# dhtsensor.net
KiCad netlist of a schematic drawn in EAGLE
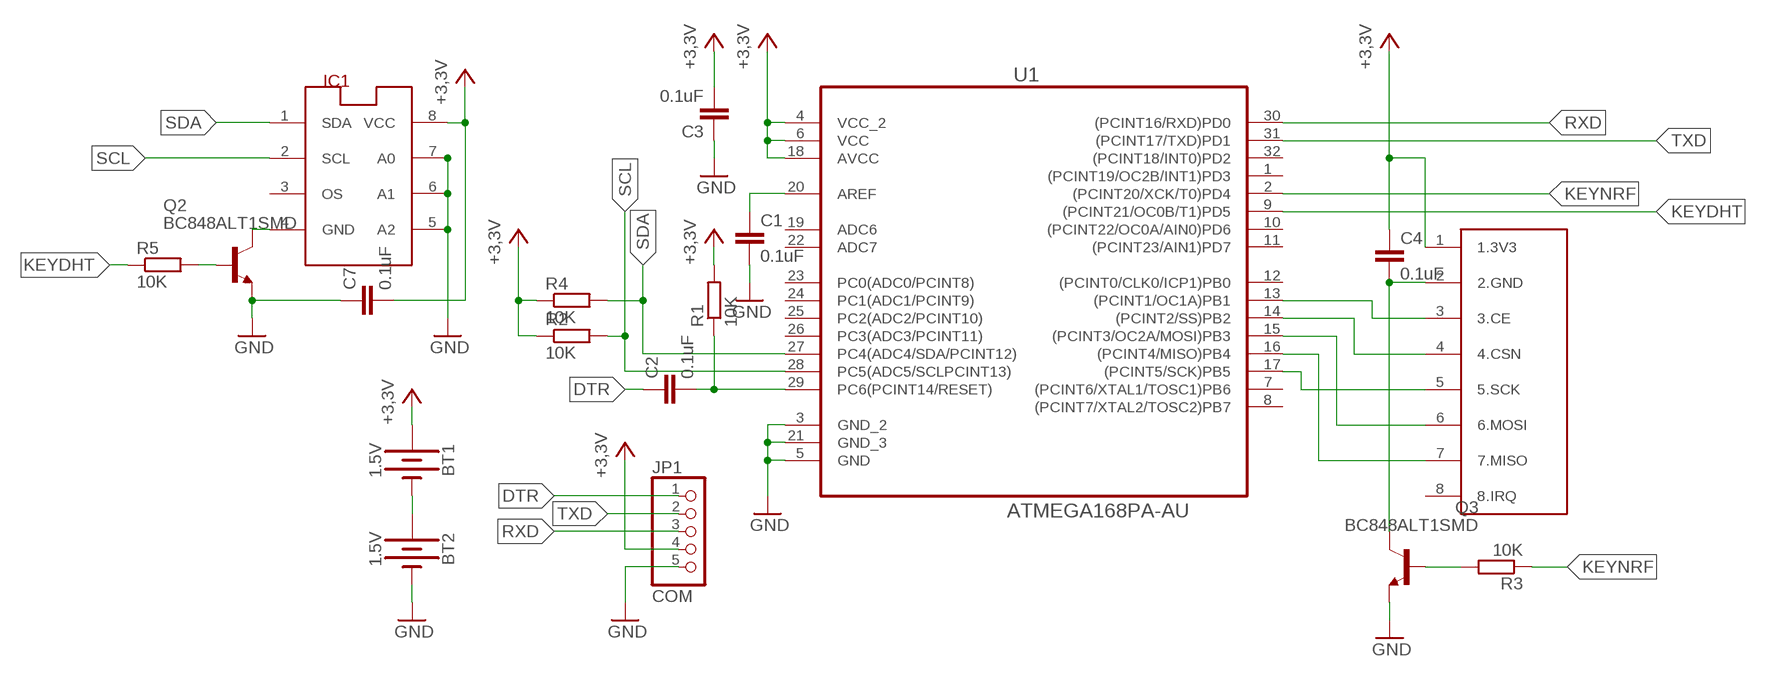
[diagram p0: schematic, sheet 1]

(export (version "E")
  (design (tool "Eeschema 10.0.6"))
  (components
    (comp (ref "BT1")
      (value "1.5V")
      (footprint "eagle-import:BATTERY-AAA-KIT")
      (libsource (lib "eagle-import") (part "BATTERY-AAA_KIT"))
    )
    (comp (ref "BT2")
      (value "1.5V")
      (footprint "eagle-import:BATTERY-AAA-KIT")
      (libsource (lib "eagle-import") (part "BATTERY-AAA_KIT"))
    )
    (comp (ref "C1")
      (value "0.1uF")
      (footprint "eagle-import:C1206")
      (libsource (lib "eagle-import") (part "C-EUC1206"))
    )
    (comp (ref "C2")
      (value "0.1uF")
      (footprint "eagle-import:C1206")
      (libsource (lib "eagle-import") (part "C-EUC1206"))
    )
    (comp (ref "C3")
      (value "0.1uF")
      (footprint "eagle-import:C1206")
      (libsource (lib "eagle-import") (part "C-EUC1206"))
    )
    (comp (ref "C4")
      (value "0.1uF")
      (footprint "eagle-import:C1206")
      (libsource (lib "eagle-import") (part "C-EUC1206"))
    )
    (comp (ref "C7")
      (value "0.1uF")
      (footprint "eagle-import:C1206")
      (libsource (lib "eagle-import") (part "C-EUC1206"))
    )
    (comp (ref "IC1")
      (value "LM75_ICN")
      (footprint "eagle-import:SO8_LM75")
      (libsource (lib "eagle-import") (part "LM75_ICN"))
    )
    (comp (ref "JP1")
      (value "COM")
      (footprint "eagle-import:1X05")
      (libsource (lib "eagle-import") (part "PINHD-1X5"))
    )
    (comp (ref "Q2")
      (value "BC848ALT1SMD")
      (footprint "eagle-import:SOT23")
      (libsource (lib "eagle-import") (part "BC848SMDALT1"))
    )
    (comp (ref "Q3")
      (value "BC848ALT1SMD")
      (footprint "eagle-import:SOT23")
      (libsource (lib "eagle-import") (part "BC848SMDALT1"))
    )
    (comp (ref "R1")
      (value "10K")
      (footprint "eagle-import:R1206")
      (libsource (lib "eagle-import") (part "R-EU_R1206"))
    )
    (comp (ref "R2")
      (value "10K")
      (footprint "eagle-import:R1206")
      (libsource (lib "eagle-import") (part "R-EU_R1206"))
    )
    (comp (ref "R3")
      (value "10K")
      (footprint "eagle-import:R1206")
      (libsource (lib "eagle-import") (part "R-EU_R1206"))
    )
    (comp (ref "R4")
      (value "10K")
      (footprint "eagle-import:R1206")
      (libsource (lib "eagle-import") (part "R-EU_R1206"))
    )
    (comp (ref "R5")
      (value "10K")
      (footprint "eagle-import:R1206")
      (libsource (lib "eagle-import") (part "R-EU_R1206"))
    )
    (comp (ref "U$9")
      (value "NRF24L01+")
      (footprint "eagle-import:NRF24L01+")
      (libsource (lib "eagle-import") (part "NRF24L01+"))
    )
    (comp (ref "U1")
      (value "ATMEGA168PA-AU")
      (footprint "eagle-import:QFP80P900X900X120-32N")
      (fields (field (name "MF") "Atmel"))
      (libsource (lib "eagle-import") (part "ATMEGA168PA-AU"))
    )
  )
  (nets
    (net (code "1") (name "+3,3V") (class "Default")
      (node (ref "BT1") (pin "PWR@1") (pinfunction "+_PWR@1") (pintype "power_in"))
      (node (ref "C3") (pin "2") (pinfunction "2_2") (pintype "passive"))
      (node (ref "C4") (pin "1") (pinfunction "1_1") (pintype "passive"))
      (node (ref "C7") (pin "2") (pinfunction "2_2") (pintype "passive"))
      (node (ref "IC1") (pin "8") (pinfunction "VCC_8") (pintype "power_in"))
      (node (ref "JP1") (pin "4") (pinfunction "4_4") (pintype "passive"))
      (node (ref "R1") (pin "2") (pinfunction "2_2") (pintype "passive"))
      (node (ref "R2") (pin "1") (pinfunction "1_1") (pintype "passive"))
      (node (ref "R4") (pin "1") (pinfunction "1_1") (pintype "passive"))
      (node (ref "U$9") (pin "1") (pinfunction "1.3V3_1") (pintype "bidirectional"))
      (node (ref "U1") (pin "18") (pinfunction "AVCC_18") (pintype "power_in"))
      (node (ref "U1") (pin "4") (pinfunction "VCC_2_4") (pintype "power_in"))
      (node (ref "U1") (pin "6") (pinfunction "VCC_6") (pintype "power_in"))
    )
    (net (code "2") (name "DTR") (class "Default")
      (node (ref "C2") (pin "1") (pinfunction "1_1") (pintype "passive"))
      (node (ref "JP1") (pin "1") (pinfunction "1_1") (pintype "passive"))
    )
    (net (code "3") (name "GND") (class "Default")
      (node (ref "BT2") (pin "GND@1") (pinfunction "-_GND@1") (pintype "power_in"))
      (node (ref "C1") (pin "2") (pinfunction "2_2") (pintype "passive"))
      (node (ref "C3") (pin "1") (pinfunction "1_1") (pintype "passive"))
      (node (ref "C7") (pin "1") (pinfunction "1_1") (pintype "passive"))
      (node (ref "IC1") (pin "5") (pinfunction "A2_5") (pintype "input"))
      (node (ref "IC1") (pin "6") (pinfunction "A1_6") (pintype "input"))
      (node (ref "IC1") (pin "7") (pinfunction "A0_7") (pintype "input"))
      (node (ref "JP1") (pin "5") (pinfunction "5_5") (pintype "passive"))
      (node (ref "Q2") (pin "2") (pinfunction "E_2") (pintype "passive"))
      (node (ref "Q3") (pin "2") (pinfunction "E_2") (pintype "passive"))
      (node (ref "U1") (pin "21") (pinfunction "GND_3_21") (pintype "passive"))
      (node (ref "U1") (pin "3") (pinfunction "GND_2_3") (pintype "passive"))
      (node (ref "U1") (pin "5") (pinfunction "GND_5") (pintype "passive"))
    )
    (net (code "4") (name "KEYDHT") (class "Default")
      (node (ref "R5") (pin "1") (pinfunction "1_1") (pintype "passive"))
      (node (ref "U1") (pin "9") (pinfunction "(PCINT21/OC0B/T1)PD5_9") (pintype "bidirectional"))
    )
    (net (code "5") (name "KEYNRF") (class "Default")
      (node (ref "R3") (pin "1") (pinfunction "1_1") (pintype "passive"))
      (node (ref "U1") (pin "2") (pinfunction "(PCINT20/XCK/T0)PD4_2") (pintype "bidirectional"))
    )
    (net (code "6") (name "Net-(BT1--)") (class "Default")
      (node (ref "BT1") (pin "GND@1") (pinfunction "-_GND@1") (pintype "power_in"))
      (node (ref "BT2") (pin "PWR@1") (pinfunction "+_PWR@1") (pintype "power_in"))
    )
    (net (code "7") (name "Net-(IC1-GND)") (class "Default")
      (node (ref "IC1") (pin "4") (pinfunction "GND_4") (pintype "power_in"))
      (node (ref "Q2") (pin "3") (pinfunction "C_3") (pintype "passive"))
    )
    (net (code "8") (name "Net-(Q2-B)") (class "Default")
      (node (ref "Q2") (pin "1") (pinfunction "B_1") (pintype "passive"))
      (node (ref "R5") (pin "2") (pinfunction "2_2") (pintype "passive"))
    )
    (net (code "9") (name "Net-(Q3-B)") (class "Default")
      (node (ref "Q3") (pin "1") (pinfunction "B_1") (pintype "passive"))
      (node (ref "R3") (pin "2") (pinfunction "2_2") (pintype "passive"))
    )
    (net (code "10") (name "Net-(Q3-C)") (class "Default")
      (node (ref "C4") (pin "2") (pinfunction "2_2") (pintype "passive"))
      (node (ref "Q3") (pin "3") (pinfunction "C_3") (pintype "passive"))
      (node (ref "U$9") (pin "2") (pinfunction "2.GND_2") (pintype "bidirectional"))
    )
    (net (code "11") (name "Net-(U$9-3.CE)") (class "Default")
      (node (ref "U$9") (pin "3") (pinfunction "3.CE_3") (pintype "bidirectional"))
      (node (ref "U1") (pin "13") (pinfunction "(PCINT1/OC1A)PB1_13") (pintype "bidirectional"))
    )
    (net (code "12") (name "Net-(U$9-4.CSN)") (class "Default")
      (node (ref "U$9") (pin "4") (pinfunction "4.CSN_4") (pintype "bidirectional"))
      (node (ref "U1") (pin "14") (pinfunction "(PCINT2/SS)PB2_14") (pintype "bidirectional"))
    )
    (net (code "13") (name "Net-(U$9-5.SCK)") (class "Default")
      (node (ref "U$9") (pin "5") (pinfunction "5.SCK_5") (pintype "bidirectional"))
      (node (ref "U1") (pin "17") (pinfunction "(PCINT5/SCK)PB5_17") (pintype "bidirectional"))
    )
    (net (code "14") (name "Net-(U$9-6.MOSI)") (class "Default")
      (node (ref "U$9") (pin "6") (pinfunction "6.MOSI_6") (pintype "bidirectional"))
      (node (ref "U1") (pin "15") (pinfunction "(PCINT3/OC2A/MOSI)PB3_15") (pintype "bidirectional"))
    )
    (net (code "15") (name "Net-(U$9-7.MISO)") (class "Default")
      (node (ref "U$9") (pin "7") (pinfunction "7.MISO_7") (pintype "bidirectional"))
      (node (ref "U1") (pin "16") (pinfunction "(PCINT4/MISO)PB4_16") (pintype "bidirectional"))
    )
    (net (code "16") (name "Net-(U1-AREF)") (class "Default")
      (node (ref "C1") (pin "1") (pinfunction "1_1") (pintype "passive"))
      (node (ref "U1") (pin "20") (pinfunction "AREF_20") (pintype "input"))
    )
    (net (code "17") (name "Net-(U1-PC6(PCINT14{slash}RESET))") (class "Default")
      (node (ref "C2") (pin "2") (pinfunction "2_2") (pintype "passive"))
      (node (ref "R1") (pin "1") (pinfunction "1_1") (pintype "passive"))
      (node (ref "U1") (pin "29") (pinfunction "PC6(PCINT14/RESET)_29") (pintype "bidirectional"))
    )
    (net (code "18") (name "RXD") (class "Default")
      (node (ref "JP1") (pin "3") (pinfunction "3_3") (pintype "passive"))
      (node (ref "U1") (pin "30") (pinfunction "(PCINT16/RXD)PD0_30") (pintype "bidirectional"))
    )
    (net (code "19") (name "SCL") (class "Default")
      (node (ref "IC1") (pin "2") (pinfunction "SCL_2") (pintype "bidirectional"))
      (node (ref "R2") (pin "2") (pinfunction "2_2") (pintype "passive"))
      (node (ref "U1") (pin "28") (pinfunction "PC5(ADC5/SCLPCINT13)_28") (pintype "bidirectional"))
    )
    (net (code "20") (name "SDA") (class "Default")
      (node (ref "IC1") (pin "1") (pinfunction "SDA_1") (pintype "bidirectional"))
      (node (ref "R4") (pin "2") (pinfunction "2_2") (pintype "passive"))
      (node (ref "U1") (pin "27") (pinfunction "PC4(ADC4/SDA/PCINT12)_27") (pintype "bidirectional"))
    )
    (net (code "21") (name "TXD") (class "Default")
      (node (ref "JP1") (pin "2") (pinfunction "2_2") (pintype "passive"))
      (node (ref "U1") (pin "31") (pinfunction "(PCINT17/TXD)PD1_31") (pintype "bidirectional"))
    )
    (net (code "22") (name "unconnected-(IC1-OS-Pad3)") (class "Default")
      (node (ref "IC1") (pin "3") (pinfunction "OS_3") (pintype "output"))
    )
    (net (code "23") (name "unconnected-(U$9-8.IRQ-Pad8)") (class "Default")
      (node (ref "U$9") (pin "8") (pinfunction "8.IRQ_8") (pintype "bidirectional"))
    )
    (net (code "24") (name "unconnected-(U1-(PCINT0{slash}CLK0{slash}ICP1)PB0-Pad12)") (class "Default")
      (node (ref "U1") (pin "12") (pinfunction "(PCINT0/CLK0/ICP1)PB0_12") (pintype "bidirectional"))
    )
    (net (code "25") (name "unconnected-(U1-(PCINT6{slash}XTAL1{slash}TOSC1)PB6-Pad7)") (class "Default")
      (node (ref "U1") (pin "7") (pinfunction "(PCINT6/XTAL1/TOSC1)PB6_7") (pintype "bidirectional"))
    )
    (net (code "26") (name "unconnected-(U1-(PCINT7{slash}XTAL2{slash}TOSC2)PB7-Pad8)") (class "Default")
      (node (ref "U1") (pin "8") (pinfunction "(PCINT7/XTAL2/TOSC2)PB7_8") (pintype "bidirectional"))
    )
    (net (code "27") (name "unconnected-(U1-(PCINT18{slash}INT0)PD2-Pad32)") (class "Default")
      (node (ref "U1") (pin "32") (pinfunction "(PCINT18/INT0)PD2_32") (pintype "bidirectional"))
    )
    (net (code "28") (name "unconnected-(U1-(PCINT19{slash}OC2B{slash}INT1)PD3-Pad1)") (class "Default")
      (node (ref "U1") (pin "1") (pinfunction "(PCINT19/OC2B/INT1)PD3_1") (pintype "bidirectional"))
    )
    (net (code "29") (name "unconnected-(U1-(PCINT22{slash}OC0A{slash}AIN0)PD6-Pad10)") (class "Default")
      (node (ref "U1") (pin "10") (pinfunction "(PCINT22/OC0A/AIN0)PD6_10") (pintype "bidirectional"))
    )
    (net (code "30") (name "unconnected-(U1-(PCINT23{slash}AIN1)PD7-Pad11)") (class "Default")
      (node (ref "U1") (pin "11") (pinfunction "(PCINT23/AIN1)PD7_11") (pintype "bidirectional"))
    )
    (net (code "31") (name "unconnected-(U1-ADC6-Pad19)") (class "Default")
      (node (ref "U1") (pin "19") (pinfunction "ADC6_19") (pintype "input"))
    )
    (net (code "32") (name "unconnected-(U1-ADC7-Pad22)") (class "Default")
      (node (ref "U1") (pin "22") (pinfunction "ADC7_22") (pintype "input"))
    )
    (net (code "33") (name "unconnected-(U1-PC0(ADC0{slash}PCINT8)-Pad23)") (class "Default")
      (node (ref "U1") (pin "23") (pinfunction "PC0(ADC0/PCINT8)_23") (pintype "bidirectional"))
    )
    (net (code "34") (name "unconnected-(U1-PC1(ADC1{slash}PCINT9)-Pad24)") (class "Default")
      (node (ref "U1") (pin "24") (pinfunction "PC1(ADC1/PCINT9)_24") (pintype "bidirectional"))
    )
    (net (code "35") (name "unconnected-(U1-PC2(ADC2{slash}PCINT10)-Pad25)") (class "Default")
      (node (ref "U1") (pin "25") (pinfunction "PC2(ADC2/PCINT10)_25") (pintype "bidirectional"))
    )
    (net (code "36") (name "unconnected-(U1-PC3(ADC3{slash}PCINT11)-Pad26)") (class "Default")
      (node (ref "U1") (pin "26") (pinfunction "PC3(ADC3/PCINT11)_26") (pintype "bidirectional"))
    )
  )
)
